# ProPrj_MPY634__2025-07-24.net
KiCad netlist of a schematic drawn in EasyEDA Pro
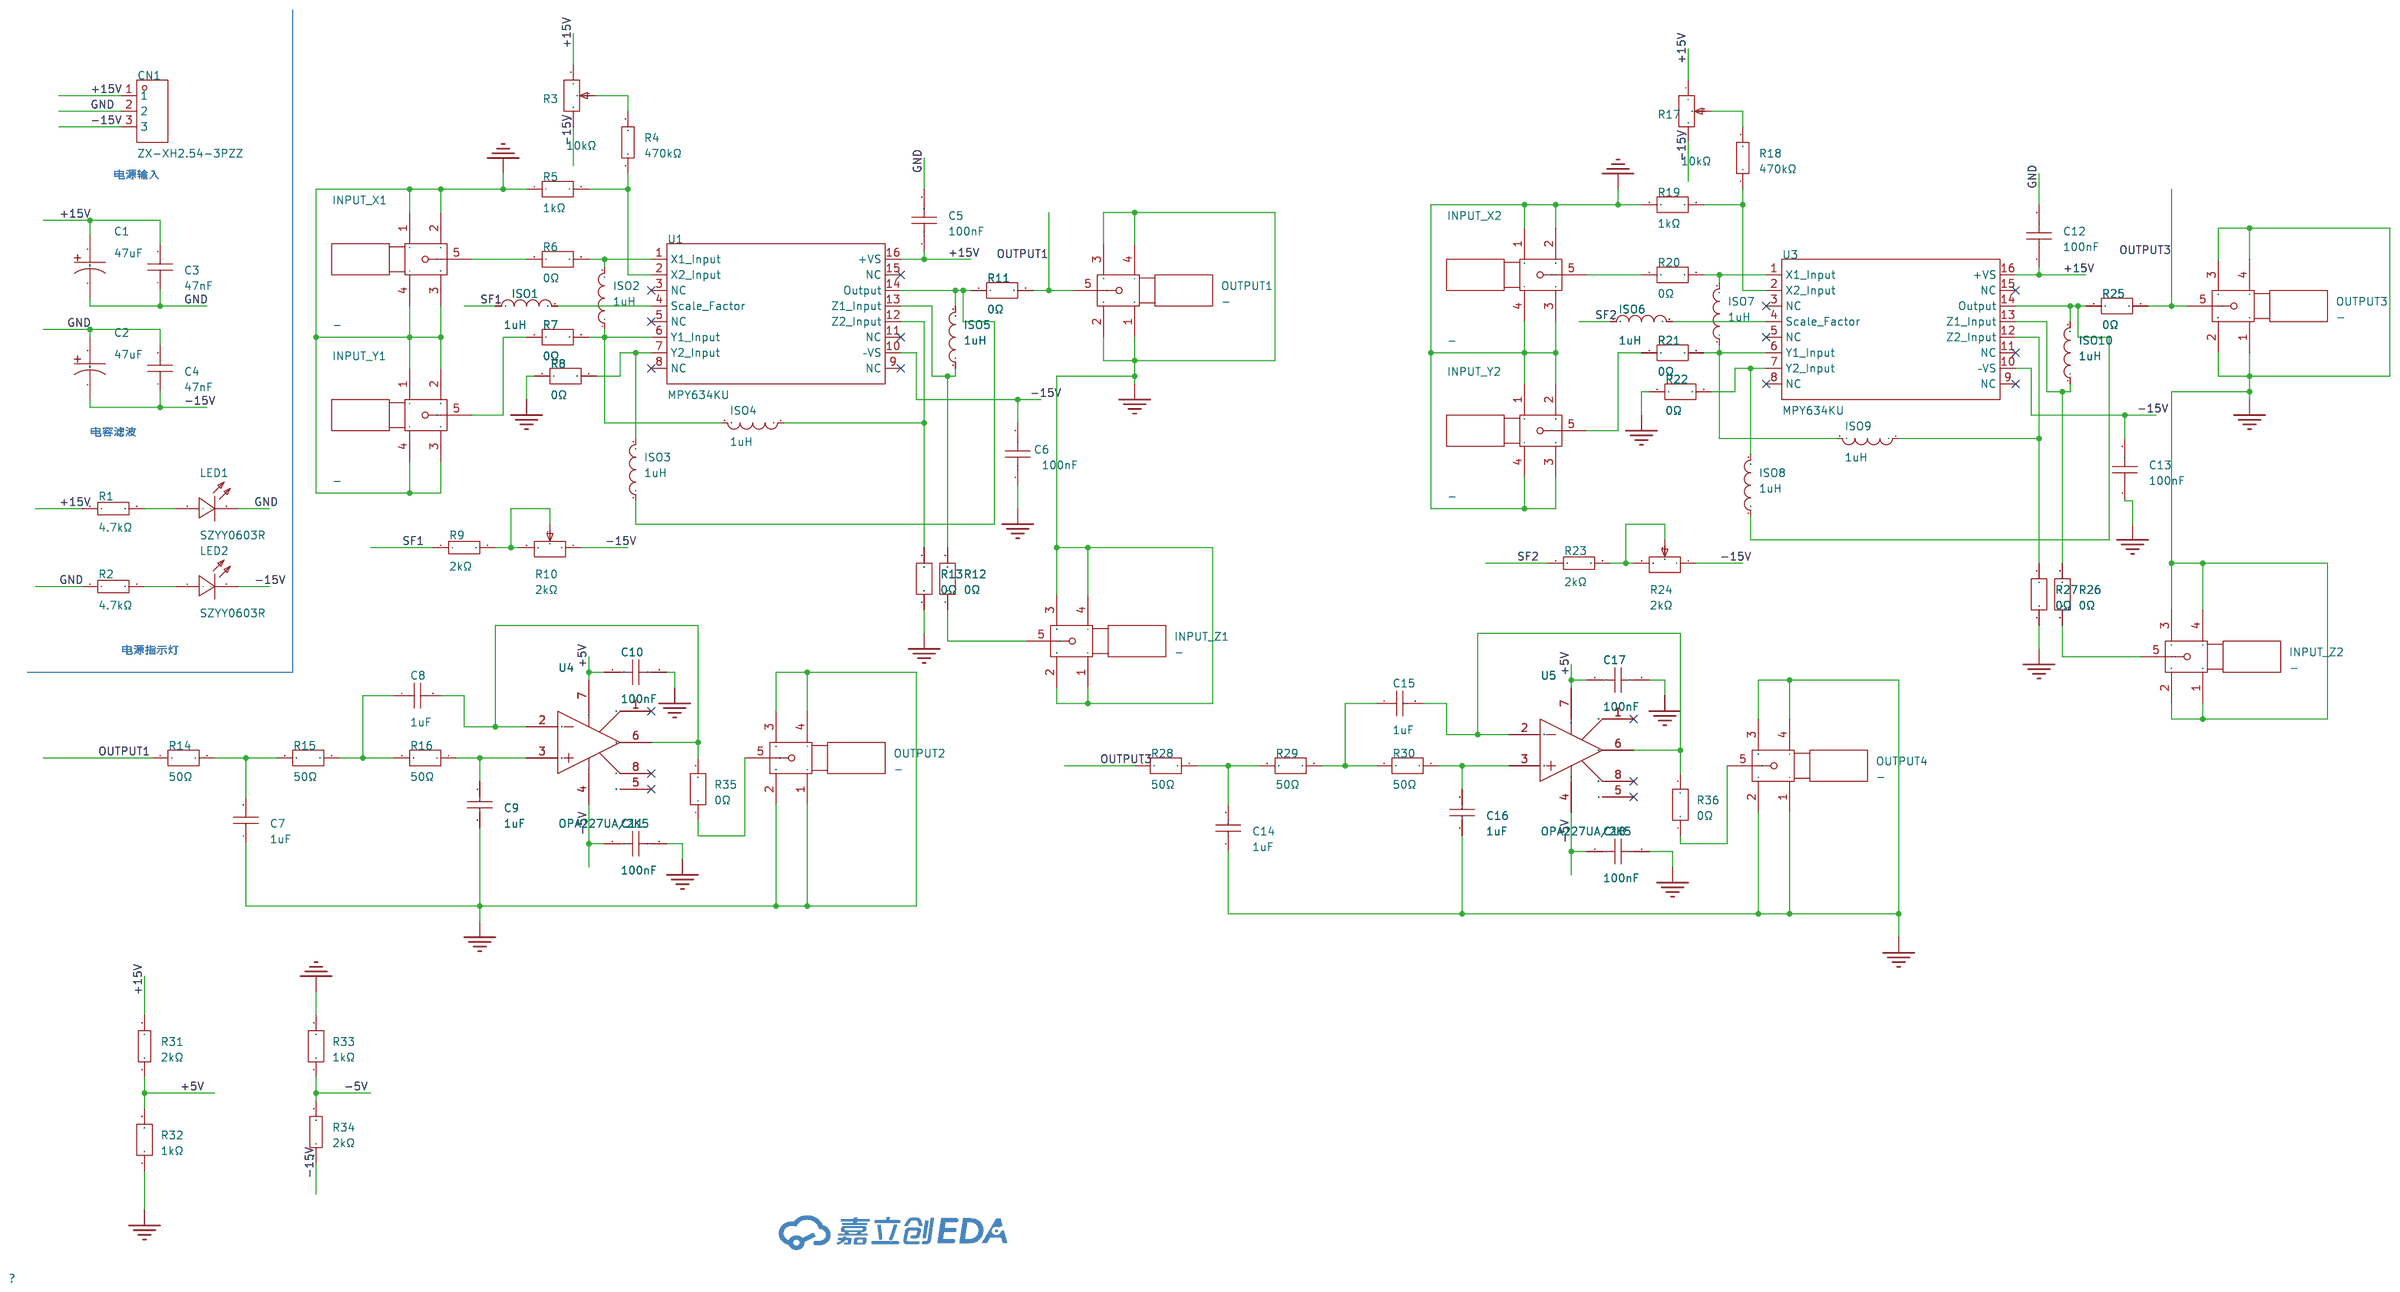
[diagram p0: schematic sheet]

(export (version "E")
  (design (tool "Eeschema 10.0.6"))
  (components
    (comp (ref "C1")
      (value "47uF")
      (footprint "easyedapro:CAP-TH_BD5.0-P2.00-D0.8-FD")
      (description "容值:47uF;精度:±20%;额定电压:25V;纹波电流:250mA@100kHz;等效串联电阻(ESR):300mΩ@100kHz;")
      (fields
        (field (name "Manufacturer Part") "NXB25V47M5*11 2.5TP")
        (field (name "Manufacturer") "SAMYOUNG(韩国三莹)")
      )
      (libsource (lib "easyedapro") (part "NXB25VB47M5*11_2.5TP"))
    )
    (comp (ref "C2")
      (value "47uF")
      (footprint "easyedapro:CAP-TH_BD5.0-P2.00-D0.8-FD")
      (description "容值:47uF;精度:±20%;额定电压:25V;纹波电流:250mA@100kHz;等效串联电阻(ESR):300mΩ@100kHz;")
      (fields
        (field (name "Manufacturer Part") "NXB25V47M5*11 2.5TP")
        (field (name "Manufacturer") "SAMYOUNG(韩国三莹)")
      )
      (libsource (lib "easyedapro") (part "NXB25VB47M5*11_2.5TP"))
    )
    (comp (ref "C3")
      (value "47nF")
      (footprint "easyedapro:C0805")
      (description "容值:47nF;精度:±10%;额定电压:50V;材质(温度系数):X7R;")
      (fields
        (field (name "Manufacturer Part") "CL21B473KBCNNNC")
        (field (name "Manufacturer") "SAMSUNG(三星)")
      )
      (libsource (lib "easyedapro") (part "CL21B473KBCNNNC"))
    )
    (comp (ref "C4")
      (value "47nF")
      (footprint "easyedapro:C0805")
      (description "容值:47nF;精度:±10%;额定电压:50V;材质(温度系数):X7R;")
      (fields
        (field (name "Manufacturer Part") "CL21B473KBCNNNC")
        (field (name "Manufacturer") "SAMSUNG(三星)")
      )
      (libsource (lib "easyedapro") (part "CL21B473KBCNNNC"))
    )
    (comp (ref "C5")
      (value "100nF")
      (footprint "easyedapro:C0805")
      (description "容值:100nF;精度:±10%;额定电压:50V;材质(温度系数):X7R;")
      (fields
        (field (name "Manufacturer Part") "CC0805KRX7R9BB104")
        (field (name "Manufacturer") "YAGEO(国巨)")
      )
      (libsource (lib "easyedapro") (part "CC0805KRX7R9BB104"))
    )
    (comp (ref "C6")
      (value "100nF")
      (footprint "easyedapro:C0805")
      (description "容值:100nF;精度:±10%;额定电压:50V;材质(温度系数):X7R;")
      (fields
        (field (name "Manufacturer Part") "CC0805KRX7R9BB104")
        (field (name "Manufacturer") "YAGEO(国巨)")
      )
      (libsource (lib "easyedapro") (part "CC0805KRX7R9BB104"))
    )
    (comp (ref "C7")
      (value "1uF")
      (footprint "easyedapro:C0805")
      (description "容值:1uF;精度:±10%;额定电压:50V;材质(温度系数):X7R;")
      (fields
        (field (name "Manufacturer Part") "CL21B105KBFNNNE")
        (field (name "Manufacturer") "SAMSUNG(三星)")
      )
      (libsource (lib "easyedapro") (part "CL21B105KBFNNNE"))
    )
    (comp (ref "C8")
      (value "1uF")
      (footprint "easyedapro:C0805")
      (description "容值:1uF;精度:±10%;额定电压:50V;材质(温度系数):X7R;")
      (fields
        (field (name "Manufacturer Part") "CL21B105KBFNNNE")
        (field (name "Manufacturer") "SAMSUNG(三星)")
      )
      (libsource (lib "easyedapro") (part "CL21B105KBFNNNE"))
    )
    (comp (ref "C9")
      (value "1uF")
      (footprint "easyedapro:C0805")
      (description "容值:1uF;精度:±10%;额定电压:50V;材质(温度系数):X7R;")
      (fields
        (field (name "Manufacturer Part") "CL21B105KBFNNNE")
        (field (name "Manufacturer") "SAMSUNG(三星)")
      )
      (libsource (lib "easyedapro") (part "CL21B105KBFNNNE"))
    )
    (comp (ref "C10")
      (value "100nF")
      (footprint "easyedapro:C0805")
      (description "容值:100nF;精度:±10%;额定电压:50V;材质(温度系数):X7R;")
      (fields
        (field (name "Manufacturer Part") "CC0805KRX7R9BB104")
        (field (name "Manufacturer") "YAGEO(国巨)")
      )
      (libsource (lib "easyedapro") (part "CC0805KRX7R9BB104"))
    )
    (comp (ref "C11")
      (value "100nF")
      (footprint "easyedapro:C0805")
      (description "容值:100nF;精度:±10%;额定电压:50V;材质(温度系数):X7R;")
      (fields
        (field (name "Manufacturer Part") "CC0805KRX7R9BB104")
        (field (name "Manufacturer") "YAGEO(国巨)")
      )
      (libsource (lib "easyedapro") (part "CC0805KRX7R9BB104"))
    )
    (comp (ref "C12")
      (value "100nF")
      (footprint "easyedapro:C0805")
      (description "容值:100nF;精度:±10%;额定电压:50V;材质(温度系数):X7R;")
      (fields
        (field (name "Manufacturer Part") "CC0805KRX7R9BB104")
        (field (name "Manufacturer") "YAGEO(国巨)")
      )
      (libsource (lib "easyedapro") (part "CC0805KRX7R9BB104"))
    )
    (comp (ref "C13")
      (value "100nF")
      (footprint "easyedapro:C0805")
      (description "容值:100nF;精度:±10%;额定电压:50V;材质(温度系数):X7R;")
      (fields
        (field (name "Manufacturer Part") "CC0805KRX7R9BB104")
        (field (name "Manufacturer") "YAGEO(国巨)")
      )
      (libsource (lib "easyedapro") (part "CC0805KRX7R9BB104"))
    )
    (comp (ref "C14")
      (value "1uF")
      (footprint "easyedapro:C0805")
      (description "容值:1uF;精度:±10%;额定电压:50V;材质(温度系数):X7R;")
      (fields
        (field (name "Manufacturer Part") "CL21B105KBFNNNE")
        (field (name "Manufacturer") "SAMSUNG(三星)")
      )
      (libsource (lib "easyedapro") (part "CL21B105KBFNNNE"))
    )
    (comp (ref "C15")
      (value "1uF")
      (footprint "easyedapro:C0805")
      (description "容值:1uF;精度:±10%;额定电压:50V;材质(温度系数):X7R;")
      (fields
        (field (name "Manufacturer Part") "CL21B105KBFNNNE")
        (field (name "Manufacturer") "SAMSUNG(三星)")
      )
      (libsource (lib "easyedapro") (part "CL21B105KBFNNNE"))
    )
    (comp (ref "C16")
      (value "1uF")
      (footprint "easyedapro:C0805")
      (description "容值:1uF;精度:±10%;额定电压:50V;材质(温度系数):X7R;")
      (fields
        (field (name "Manufacturer Part") "CL21B105KBFNNNE")
        (field (name "Manufacturer") "SAMSUNG(三星)")
      )
      (libsource (lib "easyedapro") (part "CL21B105KBFNNNE"))
    )
    (comp (ref "C17")
      (value "100nF")
      (footprint "easyedapro:C0805")
      (description "容值:100nF;精度:±10%;额定电压:50V;材质(温度系数):X7R;")
      (fields
        (field (name "Manufacturer Part") "CC0805KRX7R9BB104")
        (field (name "Manufacturer") "YAGEO(国巨)")
      )
      (libsource (lib "easyedapro") (part "CC0805KRX7R9BB104"))
    )
    (comp (ref "C18")
      (value "100nF")
      (footprint "easyedapro:C0805")
      (description "容值:100nF;精度:±10%;额定电压:50V;材质(温度系数):X7R;")
      (fields
        (field (name "Manufacturer Part") "CC0805KRX7R9BB104")
        (field (name "Manufacturer") "YAGEO(国巨)")
      )
      (libsource (lib "easyedapro") (part "CC0805KRX7R9BB104"))
    )
    (comp (ref "CN1")
      (value "ZX-XH2.54-3PZZ")
      (footprint "easyedapro:CONN-TH_3P-P2.54_2501S-3P")
      (fields (field (name "Manufacturer") "Megastar(兆星)"))
      (libsource (lib "easyedapro") (part "ZX-XH2.54-3PZZ"))
    )
    (comp (ref "INPUT_X1")
      (value "-")
      (footprint "easyedapro:SMA-SMD_BWSMA-KE-P001")
      (description "连接器类型:板端;接口类型:内孔;端口数量:1;接口直径:5.2mm;接口长度/高度:-;频率:-;射频系列:SMA;阻抗:50Ω;样式:偏脚;工作温度:-;")
      (fields
        (field (name "Manufacturer Part") "BWSMA-KE-P001")
        (field (name "Manufacturer") "BAT WIRELESS(蝙蝠无线)")
      )
      (libsource (lib "easyedapro") (part "BWSMA-KE-P001"))
    )
    (comp (ref "INPUT_X2")
      (value "-")
      (footprint "easyedapro:SMA-SMD_BWSMA-KE-P001")
      (description "连接器类型:板端;接口类型:内孔;端口数量:1;接口直径:5.2mm;接口长度/高度:-;频率:-;射频系列:SMA;阻抗:50Ω;样式:偏脚;工作温度:-;")
      (fields
        (field (name "Manufacturer Part") "BWSMA-KE-P001")
        (field (name "Manufacturer") "BAT WIRELESS(蝙蝠无线)")
      )
      (libsource (lib "easyedapro") (part "BWSMA-KE-P001"))
    )
    (comp (ref "INPUT_Y1")
      (value "-")
      (footprint "easyedapro:SMA-SMD_BWSMA-KE-P001")
      (description "连接器类型:板端;接口类型:内孔;端口数量:1;接口直径:5.2mm;接口长度/高度:-;频率:-;射频系列:SMA;阻抗:50Ω;样式:偏脚;工作温度:-;")
      (fields
        (field (name "Manufacturer Part") "BWSMA-KE-P001")
        (field (name "Manufacturer") "BAT WIRELESS(蝙蝠无线)")
      )
      (libsource (lib "easyedapro") (part "BWSMA-KE-P001"))
    )
    (comp (ref "INPUT_Y2")
      (value "-")
      (footprint "easyedapro:SMA-SMD_BWSMA-KE-P001")
      (description "连接器类型:板端;接口类型:内孔;端口数量:1;接口直径:5.2mm;接口长度/高度:-;频率:-;射频系列:SMA;阻抗:50Ω;样式:偏脚;工作温度:-;")
      (fields
        (field (name "Manufacturer Part") "BWSMA-KE-P001")
        (field (name "Manufacturer") "BAT WIRELESS(蝙蝠无线)")
      )
      (libsource (lib "easyedapro") (part "BWSMA-KE-P001"))
    )
    (comp (ref "INPUT_Z1")
      (value "-")
      (footprint "easyedapro:SMA-SMD_BWSMA-KE-P001")
      (description "连接器类型:板端;接口类型:内孔;端口数量:1;接口直径:5.2mm;接口长度/高度:-;频率:-;射频系列:SMA;阻抗:50Ω;样式:偏脚;工作温度:-;")
      (fields
        (field (name "Manufacturer Part") "BWSMA-KE-P001")
        (field (name "Manufacturer") "BAT WIRELESS(蝙蝠无线)")
      )
      (libsource (lib "easyedapro") (part "BWSMA-KE-P001"))
    )
    (comp (ref "INPUT_Z2")
      (value "-")
      (footprint "easyedapro:SMA-SMD_BWSMA-KE-P001")
      (description "连接器类型:板端;接口类型:内孔;端口数量:1;接口直径:5.2mm;接口长度/高度:-;频率:-;射频系列:SMA;阻抗:50Ω;样式:偏脚;工作温度:-;")
      (fields
        (field (name "Manufacturer Part") "BWSMA-KE-P001")
        (field (name "Manufacturer") "BAT WIRELESS(蝙蝠无线)")
      )
      (libsource (lib "easyedapro") (part "BWSMA-KE-P001"))
    )
    (comp (ref "ISO1")
      (value "1uH")
      (footprint "easyedapro:IND-SMD_L1.0-W0.6")
      (description "电感值:1uH;精度:±20%;额定电流:270mA;饱和电流(Isat):-;")
      (fields (field (name "Manufacturer Part") "LQW15CN1R0M10D") (field (name "Manufacturer") "muRata(村田)"))
      (libsource (lib "easyedapro") (part "LQW15CN1R0M10D"))
    )
    (comp (ref "ISO2")
      (value "1uH")
      (footprint "easyedapro:IND-SMD_L1.0-W0.6")
      (description "电感值:1uH;精度:±20%;额定电流:270mA;饱和电流(Isat):-;")
      (fields (field (name "Manufacturer Part") "LQW15CN1R0M10D") (field (name "Manufacturer") "muRata(村田)"))
      (libsource (lib "easyedapro") (part "LQW15CN1R0M10D"))
    )
    (comp (ref "ISO3")
      (value "1uH")
      (footprint "easyedapro:IND-SMD_L1.0-W0.6")
      (description "电感值:1uH;精度:±20%;额定电流:270mA;饱和电流(Isat):-;")
      (fields (field (name "Manufacturer Part") "LQW15CN1R0M10D") (field (name "Manufacturer") "muRata(村田)"))
      (libsource (lib "easyedapro") (part "LQW15CN1R0M10D"))
    )
    (comp (ref "ISO4")
      (value "1uH")
      (footprint "easyedapro:IND-SMD_L1.0-W0.6")
      (description "电感值:1uH;精度:±20%;额定电流:270mA;饱和电流(Isat):-;")
      (fields (field (name "Manufacturer Part") "LQW15CN1R0M10D") (field (name "Manufacturer") "muRata(村田)"))
      (libsource (lib "easyedapro") (part "LQW15CN1R0M10D"))
    )
    (comp (ref "ISO5")
      (value "1uH")
      (footprint "easyedapro:IND-SMD_L1.0-W0.6")
      (description "电感值:1uH;精度:±20%;额定电流:270mA;饱和电流(Isat):-;")
      (fields (field (name "Manufacturer Part") "LQW15CN1R0M10D") (field (name "Manufacturer") "muRata(村田)"))
      (libsource (lib "easyedapro") (part "LQW15CN1R0M10D"))
    )
    (comp (ref "ISO6")
      (value "1uH")
      (footprint "easyedapro:IND-SMD_L1.0-W0.6")
      (description "电感值:1uH;精度:±20%;额定电流:270mA;饱和电流(Isat):-;")
      (fields (field (name "Manufacturer Part") "LQW15CN1R0M10D") (field (name "Manufacturer") "muRata(村田)"))
      (libsource (lib "easyedapro") (part "LQW15CN1R0M10D"))
    )
    (comp (ref "ISO7")
      (value "1uH")
      (footprint "easyedapro:IND-SMD_L1.0-W0.6")
      (description "电感值:1uH;精度:±20%;额定电流:270mA;饱和电流(Isat):-;")
      (fields (field (name "Manufacturer Part") "LQW15CN1R0M10D") (field (name "Manufacturer") "muRata(村田)"))
      (libsource (lib "easyedapro") (part "LQW15CN1R0M10D"))
    )
    (comp (ref "ISO8")
      (value "1uH")
      (footprint "easyedapro:IND-SMD_L1.0-W0.6")
      (description "电感值:1uH;精度:±20%;额定电流:270mA;饱和电流(Isat):-;")
      (fields (field (name "Manufacturer Part") "LQW15CN1R0M10D") (field (name "Manufacturer") "muRata(村田)"))
      (libsource (lib "easyedapro") (part "LQW15CN1R0M10D"))
    )
    (comp (ref "ISO9")
      (value "1uH")
      (footprint "easyedapro:IND-SMD_L1.0-W0.6")
      (description "电感值:1uH;精度:±20%;额定电流:270mA;饱和电流(Isat):-;")
      (fields (field (name "Manufacturer Part") "LQW15CN1R0M10D") (field (name "Manufacturer") "muRata(村田)"))
      (libsource (lib "easyedapro") (part "LQW15CN1R0M10D"))
    )
    (comp (ref "ISO10")
      (value "1uH")
      (footprint "easyedapro:IND-SMD_L1.0-W0.6")
      (description "电感值:1uH;精度:±20%;额定电流:270mA;饱和电流(Isat):-;")
      (fields (field (name "Manufacturer Part") "LQW15CN1R0M10D") (field (name "Manufacturer") "muRata(村田)"))
      (libsource (lib "easyedapro") (part "LQW15CN1R0M10D"))
    )
    (comp (ref "LED1")
      (value "SZYY0603R")
      (footprint "easyedapro:LED0603-R-RD")
      (fields (field (name "Manufacturer") "yongyu(永裕光电)"))
      (libsource (lib "easyedapro") (part "SZYY0603R"))
    )
    (comp (ref "LED2")
      (value "SZYY0603R")
      (footprint "easyedapro:LED0603-R-RD")
      (fields (field (name "Manufacturer") "yongyu(永裕光电)"))
      (libsource (lib "easyedapro") (part "SZYY0603R"))
    )
    (comp (ref "OUTPUT1")
      (value "-")
      (footprint "easyedapro:SMA-SMD_BWSMA-KE-P001")
      (description "连接器类型:板端;接口类型:内孔;端口数量:1;接口直径:5.2mm;接口长度/高度:-;频率:-;射频系列:SMA;阻抗:50Ω;样式:偏脚;工作温度:-;")
      (fields
        (field (name "Manufacturer Part") "BWSMA-KE-P001")
        (field (name "Manufacturer") "BAT WIRELESS(蝙蝠无线)")
      )
      (libsource (lib "easyedapro") (part "BWSMA-KE-P001"))
    )
    (comp (ref "OUTPUT2")
      (value "-")
      (footprint "easyedapro:SMA-SMD_BWSMA-KE-P001")
      (description "连接器类型:板端;接口类型:内孔;端口数量:1;接口直径:5.2mm;接口长度/高度:-;频率:-;射频系列:SMA;阻抗:50Ω;样式:偏脚;工作温度:-;")
      (fields
        (field (name "Manufacturer Part") "BWSMA-KE-P001")
        (field (name "Manufacturer") "BAT WIRELESS(蝙蝠无线)")
      )
      (libsource (lib "easyedapro") (part "BWSMA-KE-P001"))
    )
    (comp (ref "OUTPUT3")
      (value "-")
      (footprint "easyedapro:SMA-SMD_BWSMA-KE-P001")
      (description "连接器类型:板端;接口类型:内孔;端口数量:1;接口直径:5.2mm;接口长度/高度:-;频率:-;射频系列:SMA;阻抗:50Ω;样式:偏脚;工作温度:-;")
      (fields
        (field (name "Manufacturer Part") "BWSMA-KE-P001")
        (field (name "Manufacturer") "BAT WIRELESS(蝙蝠无线)")
      )
      (libsource (lib "easyedapro") (part "BWSMA-KE-P001"))
    )
    (comp (ref "OUTPUT4")
      (value "-")
      (footprint "easyedapro:SMA-SMD_BWSMA-KE-P001")
      (description "连接器类型:板端;接口类型:内孔;端口数量:1;接口直径:5.2mm;接口长度/高度:-;频率:-;射频系列:SMA;阻抗:50Ω;样式:偏脚;工作温度:-;")
      (fields
        (field (name "Manufacturer Part") "BWSMA-KE-P001")
        (field (name "Manufacturer") "BAT WIRELESS(蝙蝠无线)")
      )
      (libsource (lib "easyedapro") (part "BWSMA-KE-P001"))
    )
    (comp (ref "R1")
      (value "4.7kΩ")
      (footprint "easyedapro:R0805")
      (description "电阻类型:厚膜电阻;阻值:4.7kΩ;精度:±1%;功率:125mW;最大工作电压:150V;温度系数:±100ppm/°C;")
      (fields
        (field (name "Manufacturer Part") "0805W8F4701T5E")
        (field (name "Manufacturer") "UNI-ROYAL(厚声)")
      )
      (libsource (lib "easyedapro") (part "0805W8F4701T5E"))
    )
    (comp (ref "R2")
      (value "4.7kΩ")
      (footprint "easyedapro:R0805")
      (description "电阻类型:厚膜电阻;阻值:4.7kΩ;精度:±1%;功率:125mW;最大工作电压:150V;温度系数:±100ppm/°C;")
      (fields
        (field (name "Manufacturer Part") "0805W8F4701T5E")
        (field (name "Manufacturer") "UNI-ROYAL(厚声)")
      )
      (libsource (lib "easyedapro") (part "0805W8F4701T5E"))
    )
    (comp (ref "R3")
      (value "10kΩ")
      (footprint "easyedapro:RES-ADJ-TH_3296W")
      (description "阻值:10kΩ;精度:±10%;功率:500mW;温度系数:±100ppm/°C;")
      (fields (field (name "Manufacturer Part") "3296W-1-103LF") (field (name "Manufacturer") "BOURNS"))
      (libsource (lib "easyedapro") (part "3296W-1-103LF"))
    )
    (comp (ref "R4")
      (value "470kΩ")
      (footprint "easyedapro:R0805")
      (description "电阻类型:厚膜电阻;阻值:470kΩ;精度:±1%;功率:125mW;最大工作电压:150V;温度系数:±100ppm/°C;")
      (fields
        (field (name "Manufacturer Part") "0805W8F4703T5E")
        (field (name "Manufacturer") "UNI-ROYAL(厚声)")
      )
      (libsource (lib "easyedapro") (part "0805W8F4703T5E"))
    )
    (comp (ref "R5")
      (value "1kΩ")
      (footprint "easyedapro:R0805")
      (description "电阻类型:厚膜电阻;阻值:1kΩ;精度:±5%;功率:125mW;最大工作电压:150V;温度系数:±100ppm/°C;")
      (fields (field (name "Manufacturer Part") "FRC0805J102 TS") (field (name "Manufacturer") "FOJAN(富捷)"))
      (libsource (lib "easyedapro") (part "FRC0805J102 TS"))
    )
    (comp (ref "R6")
      (value "0Ω")
      (footprint "easyedapro:R0603")
      (description "电阻类型:厚膜电阻;阻值:0Ω;精度:±5%;功率:100mW;最大工作电压:75V;")
      (fields (field (name "Manufacturer Part") "FRC0603P000 TS") (field (name "Manufacturer") "FOJAN(富捷)"))
      (libsource (lib "easyedapro") (part "FRC0603P000 TS"))
    )
    (comp (ref "R7")
      (value "0Ω")
      (footprint "easyedapro:R0603")
      (description "电阻类型:厚膜电阻;阻值:0Ω;精度:±5%;功率:100mW;最大工作电压:75V;")
      (fields (field (name "Manufacturer Part") "FRC0603P000 TS") (field (name "Manufacturer") "FOJAN(富捷)"))
      (libsource (lib "easyedapro") (part "FRC0603P000 TS"))
    )
    (comp (ref "R8")
      (value "0Ω")
      (footprint "easyedapro:R0603")
      (description "电阻类型:厚膜电阻;阻值:0Ω;精度:±5%;功率:100mW;最大工作电压:75V;")
      (fields (field (name "Manufacturer Part") "FRC0603P000 TS") (field (name "Manufacturer") "FOJAN(富捷)"))
      (libsource (lib "easyedapro") (part "FRC0603P000 TS"))
    )
    (comp (ref "R9")
      (value "2kΩ")
      (footprint "easyedapro:R0805")
      (description "电阻类型:厚膜电阻;阻值:2kΩ;精度:±1%;功率:125mW;最大工作电压:150V;温度系数:±100ppm/°C;")
      (fields
        (field (name "Manufacturer Part") "0805W8F2001T5E")
        (field (name "Manufacturer") "UNI-ROYAL(厚声)")
      )
      (libsource (lib "easyedapro") (part "0805W8F2001T5E"))
    )
    (comp (ref "R10")
      (value "2kΩ")
      (footprint "easyedapro:RES-ADJ-TH_3296W")
      (description "阻值:2kΩ;精度:±10%;")
      (fields (field (name "Manufacturer Part") "3296W-1-202LF") (field (name "Manufacturer") "BOURNS"))
      (libsource (lib "easyedapro") (part "3296W-1-202LF_C83684"))
    )
    (comp (ref "R11")
      (value "0Ω")
      (footprint "easyedapro:R0603")
      (description "电阻类型:厚膜电阻;阻值:0Ω;精度:±5%;功率:100mW;最大工作电压:75V;")
      (fields (field (name "Manufacturer Part") "FRC0603P000 TS") (field (name "Manufacturer") "FOJAN(富捷)"))
      (libsource (lib "easyedapro") (part "FRC0603P000 TS"))
    )
    (comp (ref "R12")
      (value "0Ω")
      (footprint "easyedapro:R0603")
      (description "电阻类型:厚膜电阻;阻值:0Ω;精度:±5%;功率:100mW;最大工作电压:75V;")
      (fields (field (name "Manufacturer Part") "FRC0603P000 TS") (field (name "Manufacturer") "FOJAN(富捷)"))
      (libsource (lib "easyedapro") (part "FRC0603P000 TS"))
    )
    (comp (ref "R13")
      (value "0Ω")
      (footprint "easyedapro:R0603")
      (description "电阻类型:厚膜电阻;阻值:0Ω;精度:±5%;功率:100mW;最大工作电压:75V;")
      (fields (field (name "Manufacturer Part") "FRC0603P000 TS") (field (name "Manufacturer") "FOJAN(富捷)"))
      (libsource (lib "easyedapro") (part "FRC0603P000 TS"))
    )
    (comp (ref "R14")
      (value "50Ω")
      (footprint "easyedapro:R0805")
      (description "电阻类型:薄膜电阻;阻值:50Ω;精度:±0.1%;功率:100mW;温度系数:±25ppm/°C;")
      (fields (field (name "Manufacturer Part") "TD05G50R0BT") (field (name "Manufacturer") "FH(风华)"))
      (libsource (lib "easyedapro") (part "TD05G50R0BT"))
    )
    (comp (ref "R15")
      (value "50Ω")
      (footprint "easyedapro:R0805")
      (description "电阻类型:薄膜电阻;阻值:50Ω;精度:±0.1%;功率:100mW;温度系数:±25ppm/°C;")
      (fields (field (name "Manufacturer Part") "TD05G50R0BT") (field (name "Manufacturer") "FH(风华)"))
      (libsource (lib "easyedapro") (part "TD05G50R0BT"))
    )
    (comp (ref "R16")
      (value "50Ω")
      (footprint "easyedapro:R0805")
      (description "电阻类型:薄膜电阻;阻值:50Ω;精度:±0.1%;功率:100mW;温度系数:±25ppm/°C;")
      (fields (field (name "Manufacturer Part") "TD05G50R0BT") (field (name "Manufacturer") "FH(风华)"))
      (libsource (lib "easyedapro") (part "TD05G50R0BT"))
    )
    (comp (ref "R17")
      (value "10kΩ")
      (footprint "easyedapro:RES-ADJ-TH_3296W")
      (description "阻值:10kΩ;精度:±10%;功率:500mW;温度系数:±100ppm/°C;")
      (fields (field (name "Manufacturer Part") "3296W-1-103LF") (field (name "Manufacturer") "BOURNS"))
      (libsource (lib "easyedapro") (part "3296W-1-103LF"))
    )
    (comp (ref "R18")
      (value "470kΩ")
      (footprint "easyedapro:R0805")
      (description "电阻类型:厚膜电阻;阻值:470kΩ;精度:±1%;功率:125mW;最大工作电压:150V;温度系数:±100ppm/°C;")
      (fields
        (field (name "Manufacturer Part") "0805W8F4703T5E")
        (field (name "Manufacturer") "UNI-ROYAL(厚声)")
      )
      (libsource (lib "easyedapro") (part "0805W8F4703T5E"))
    )
    (comp (ref "R19")
      (value "1kΩ")
      (footprint "easyedapro:R0805")
      (description "电阻类型:厚膜电阻;阻值:1kΩ;精度:±5%;功率:125mW;最大工作电压:150V;温度系数:±100ppm/°C;")
      (fields (field (name "Manufacturer Part") "FRC0805J102 TS") (field (name "Manufacturer") "FOJAN(富捷)"))
      (libsource (lib "easyedapro") (part "FRC0805J102 TS"))
    )
    (comp (ref "R20")
      (value "0Ω")
      (footprint "easyedapro:R0603")
      (description "电阻类型:厚膜电阻;阻值:0Ω;精度:±5%;功率:100mW;最大工作电压:75V;")
      (fields (field (name "Manufacturer Part") "FRC0603P000 TS") (field (name "Manufacturer") "FOJAN(富捷)"))
      (libsource (lib "easyedapro") (part "FRC0603P000 TS"))
    )
    (comp (ref "R21")
      (value "0Ω")
      (footprint "easyedapro:R0603")
      (description "电阻类型:厚膜电阻;阻值:0Ω;精度:±5%;功率:100mW;最大工作电压:75V;")
      (fields (field (name "Manufacturer Part") "FRC0603P000 TS") (field (name "Manufacturer") "FOJAN(富捷)"))
      (libsource (lib "easyedapro") (part "FRC0603P000 TS"))
    )
    (comp (ref "R22")
      (value "0Ω")
      (footprint "easyedapro:R0603")
      (description "电阻类型:厚膜电阻;阻值:0Ω;精度:±5%;功率:100mW;最大工作电压:75V;")
      (fields (field (name "Manufacturer Part") "FRC0603P000 TS") (field (name "Manufacturer") "FOJAN(富捷)"))
      (libsource (lib "easyedapro") (part "FRC0603P000 TS"))
    )
    (comp (ref "R23")
      (value "2kΩ")
      (footprint "easyedapro:R0805")
      (description "电阻类型:厚膜电阻;阻值:2kΩ;精度:±1%;功率:125mW;最大工作电压:150V;温度系数:±100ppm/°C;")
      (fields
        (field (name "Manufacturer Part") "0805W8F2001T5E")
        (field (name "Manufacturer") "UNI-ROYAL(厚声)")
      )
      (libsource (lib "easyedapro") (part "0805W8F2001T5E"))
    )
    (comp (ref "R24")
      (value "2kΩ")
      (footprint "easyedapro:RES-ADJ-TH_3296W")
      (description "阻值:2kΩ;精度:±10%;")
      (fields (field (name "Manufacturer Part") "3296W-1-202LF") (field (name "Manufacturer") "BOURNS"))
      (libsource (lib "easyedapro") (part "3296W-1-202LF_C83684"))
    )
    (comp (ref "R25")
      (value "0Ω")
      (footprint "easyedapro:R0603")
      (description "电阻类型:厚膜电阻;阻值:0Ω;精度:±5%;功率:100mW;最大工作电压:75V;")
      (fields (field (name "Manufacturer Part") "FRC0603P000 TS") (field (name "Manufacturer") "FOJAN(富捷)"))
      (libsource (lib "easyedapro") (part "FRC0603P000 TS"))
    )
    (comp (ref "R26")
      (value "0Ω")
      (footprint "easyedapro:R0603")
      (description "电阻类型:厚膜电阻;阻值:0Ω;精度:±5%;功率:100mW;最大工作电压:75V;")
      (fields (field (name "Manufacturer Part") "FRC0603P000 TS") (field (name "Manufacturer") "FOJAN(富捷)"))
      (libsource (lib "easyedapro") (part "FRC0603P000 TS"))
    )
    (comp (ref "R27")
      (value "0Ω")
      (footprint "easyedapro:R0603")
      (description "电阻类型:厚膜电阻;阻值:0Ω;精度:±5%;功率:100mW;最大工作电压:75V;")
      (fields (field (name "Manufacturer Part") "FRC0603P000 TS") (field (name "Manufacturer") "FOJAN(富捷)"))
      (libsource (lib "easyedapro") (part "FRC0603P000 TS"))
    )
    (comp (ref "R28")
      (value "50Ω")
      (footprint "easyedapro:R0805")
      (description "电阻类型:薄膜电阻;阻值:50Ω;精度:±0.1%;功率:100mW;温度系数:±25ppm/°C;")
      (fields (field (name "Manufacturer Part") "TD05G50R0BT") (field (name "Manufacturer") "FH(风华)"))
      (libsource (lib "easyedapro") (part "TD05G50R0BT"))
    )
    (comp (ref "R29")
      (value "50Ω")
      (footprint "easyedapro:R0805")
      (description "电阻类型:薄膜电阻;阻值:50Ω;精度:±0.1%;功率:100mW;温度系数:±25ppm/°C;")
      (fields (field (name "Manufacturer Part") "TD05G50R0BT") (field (name "Manufacturer") "FH(风华)"))
      (libsource (lib "easyedapro") (part "TD05G50R0BT"))
    )
    (comp (ref "R30")
      (value "50Ω")
      (footprint "easyedapro:R0805")
      (description "电阻类型:薄膜电阻;阻值:50Ω;精度:±0.1%;功率:100mW;温度系数:±25ppm/°C;")
      (fields (field (name "Manufacturer Part") "TD05G50R0BT") (field (name "Manufacturer") "FH(风华)"))
      (libsource (lib "easyedapro") (part "TD05G50R0BT"))
    )
    (comp (ref "R31")
      (value "2kΩ")
      (footprint "easyedapro:R0805")
      (description "电阻类型:厚膜电阻;阻值:2kΩ;精度:±1%;功率:125mW;最大工作电压:150V;温度系数:±100ppm/°C;")
      (fields
        (field (name "Manufacturer Part") "0805W8F2001T5E")
        (field (name "Manufacturer") "UNI-ROYAL(厚声)")
      )
      (libsource (lib "easyedapro") (part "0805W8F2001T5E"))
    )
    (comp (ref "R32")
      (value "1kΩ")
      (footprint "easyedapro:R0805")
      (description "电阻类型:厚膜电阻;阻值:1kΩ;精度:±5%;功率:125mW;最大工作电压:150V;温度系数:±100ppm/°C;")
      (fields (field (name "Manufacturer Part") "FRC0805J102 TS") (field (name "Manufacturer") "FOJAN(富捷)"))
      (libsource (lib "easyedapro") (part "FRC0805J102 TS"))
    )
    (comp (ref "R33")
      (value "1kΩ")
      (footprint "easyedapro:R0805")
      (description "电阻类型:厚膜电阻;阻值:1kΩ;精度:±5%;功率:125mW;最大工作电压:150V;温度系数:±100ppm/°C;")
      (fields (field (name "Manufacturer Part") "FRC0805J102 TS") (field (name "Manufacturer") "FOJAN(富捷)"))
      (libsource (lib "easyedapro") (part "FRC0805J102 TS"))
    )
    (comp (ref "R34")
      (value "2kΩ")
      (footprint "easyedapro:R0805")
      (description "电阻类型:厚膜电阻;阻值:2kΩ;精度:±1%;功率:125mW;最大工作电压:150V;温度系数:±100ppm/°C;")
      (fields
        (field (name "Manufacturer Part") "0805W8F2001T5E")
        (field (name "Manufacturer") "UNI-ROYAL(厚声)")
      )
      (libsource (lib "easyedapro") (part "0805W8F2001T5E"))
    )
    (comp (ref "R35")
      (value "0Ω")
      (footprint "easyedapro:R0603")
      (description "电阻类型:厚膜电阻;阻值:0Ω;精度:±5%;功率:100mW;最大工作电压:75V;")
      (fields (field (name "Manufacturer Part") "FRC0603P000 TS") (field (name "Manufacturer") "FOJAN(富捷)"))
      (libsource (lib "easyedapro") (part "FRC0603P000 TS"))
    )
    (comp (ref "R36")
      (value "0Ω")
      (footprint "easyedapro:R0603")
      (description "电阻类型:厚膜电阻;阻值:0Ω;精度:±5%;功率:100mW;最大工作电压:75V;")
      (fields (field (name "Manufacturer Part") "FRC0603P000 TS") (field (name "Manufacturer") "FOJAN(富捷)"))
      (libsource (lib "easyedapro") (part "FRC0603P000 TS"))
    )
    (comp (ref "U1")
      (value "MPY634KU")
      (footprint "easyedapro:SOIC-16_L10.3-W7.5-P1.27-LS10.3-BL")
      (description "象限:四象限;带宽:-;")
      (fields (field (name "Manufacturer") "TI(德州仪器)"))
      (libsource (lib "easyedapro") (part "MPY634KU"))
    )
    (comp (ref "U3")
      (value "MPY634KU")
      (footprint "easyedapro:SOIC-16_L10.3-W7.5-P1.27-LS10.3-BL")
      (description "象限:四象限;带宽:-;")
      (fields (field (name "Manufacturer") "TI(德州仪器)"))
      (libsource (lib "easyedapro") (part "MPY634KU"))
    )
    (comp (ref "U4")
      (value "OPA227UA/2K5")
      (footprint "easyedapro:SOIC-8_L4.9-W3.9-P1.27-LS6.0-BL")
      (description "放大器数:单路;增益带宽积(GBP):8MHz;输入偏置电流(Ib):2.5nA;压摆率(SR):2.3V/us;轨到轨:-;")
      (fields (field (name "Manufacturer") "TI(德州仪器)"))
      (libsource (lib "easyedapro") (part "OPA227UA/2K5"))
    )
    (comp (ref "U5")
      (value "OPA227UA/2K5")
      (footprint "easyedapro:SOIC-8_L4.9-W3.9-P1.27-LS6.0-BL")
      (description "放大器数:单路;增益带宽积(GBP):8MHz;输入偏置电流(Ib):2.5nA;压摆率(SR):2.3V/us;轨到轨:-;")
      (fields (field (name "Manufacturer") "TI(德州仪器)"))
      (libsource (lib "easyedapro") (part "OPA227UA/2K5"))
    )
  )
  (nets
    (net (code "1") (name "/+5V") (class "Default")
      (node (ref "C10") (pin "1") (pinfunction "1_1") (pintype "unspecified"))
      (node (ref "C17") (pin "1") (pinfunction "1_1") (pintype "unspecified"))
      (node (ref "R31") (pin "1") (pinfunction "1_1") (pintype "input"))
      (node (ref "R32") (pin "2") (pinfunction "2_2") (pintype "unspecified"))
      (node (ref "U4") (pin "7") (pinfunction "VCC_7") (pintype "unspecified"))
      (node (ref "U5") (pin "7") (pinfunction "VCC_7") (pintype "unspecified"))
    )
    (net (code "2") (name "/+15V") (class "Default")
      (node (ref "C1") (pin "1") (pinfunction "1_1") (pintype "unspecified"))
      (node (ref "C12") (pin "1") (pinfunction "1_1") (pintype "unspecified"))
      (node (ref "C3") (pin "2") (pinfunction "2_2") (pintype "input"))
      (node (ref "C5") (pin "1") (pinfunction "1_1") (pintype "unspecified"))
      (node (ref "CN1") (pin "1") (pinfunction "1_1") (pintype "unspecified"))
      (node (ref "R1") (pin "1") (pinfunction "1_1") (pintype "input"))
      (node (ref "R17") (pin "1") (pinfunction "1_1") (pintype "input"))
      (node (ref "R3") (pin "1") (pinfunction "1_1") (pintype "input"))
      (node (ref "R31") (pin "2") (pinfunction "2_2") (pintype "input"))
      (node (ref "U1") (pin "16") (pinfunction "+VS_16") (pintype "unspecified"))
      (node (ref "U3") (pin "16") (pinfunction "+VS_16") (pintype "unspecified"))
    )
    (net (code "3") (name "/-5V") (class "Default")
      (node (ref "C11") (pin "1") (pinfunction "1_1") (pintype "unspecified"))
      (node (ref "C18") (pin "1") (pinfunction "1_1") (pintype "unspecified"))
      (node (ref "R33") (pin "1") (pinfunction "1_1") (pintype "unspecified"))
      (node (ref "R34") (pin "2") (pinfunction "2_2") (pintype "input"))
      (node (ref "U4") (pin "4") (pinfunction "VSS_4") (pintype "unspecified"))
      (node (ref "U5") (pin "4") (pinfunction "VSS_4") (pintype "unspecified"))
    )
    (net (code "4") (name "/-15V") (class "Default")
      (node (ref "C13") (pin "2") (pinfunction "2_2") (pintype "unspecified"))
      (node (ref "C2") (pin "2") (pinfunction "2_2") (pintype "unspecified"))
      (node (ref "C4") (pin "1") (pinfunction "1_1") (pintype "input"))
      (node (ref "C6") (pin "2") (pinfunction "2_2") (pintype "unspecified"))
      (node (ref "CN1") (pin "3") (pinfunction "3_3") (pintype "unspecified"))
      (node (ref "LED2") (pin "2") (pinfunction "-_2") (pintype "unspecified"))
      (node (ref "R10") (pin "1") (pinfunction "1_1") (pintype "input"))
      (node (ref "R17") (pin "3") (pinfunction "3_3") (pintype "input"))
      (node (ref "R24") (pin "1") (pinfunction "1_1") (pintype "input"))
      (node (ref "R3") (pin "3") (pinfunction "3_3") (pintype "input"))
      (node (ref "R34") (pin "1") (pinfunction "1_1") (pintype "input"))
      (node (ref "U1") (pin "10") (pinfunction "–VS_10") (pintype "unspecified"))
      (node (ref "U3") (pin "10") (pinfunction "–VS_10") (pintype "unspecified"))
    )
    (net (code "5") (name "/OUTPUT1") (class "Default")
      (node (ref "OUTPUT1") (pin "5") (pinfunction "5_5") (pintype "unspecified"))
      (node (ref "R11") (pin "2") (pinfunction "2_2") (pintype "unspecified"))
      (node (ref "R14") (pin "1") (pinfunction "1_1") (pintype "unspecified"))
    )
    (net (code "6") (name "/OUTPUT3") (class "Default")
      (node (ref "OUTPUT3") (pin "5") (pinfunction "5_5") (pintype "unspecified"))
      (node (ref "R25") (pin "2") (pinfunction "2_2") (pintype "unspecified"))
      (node (ref "R28") (pin "1") (pinfunction "1_1") (pintype "unspecified"))
    )
    (net (code "7") (name "/SF1") (class "Default")
      (node (ref "ISO1") (pin "1") (pinfunction "1_1") (pintype "unspecified"))
      (node (ref "R9") (pin "1") (pinfunction "1_1") (pintype "input"))
    )
    (net (code "8") (name "/SF2") (class "Default")
      (node (ref "ISO6") (pin "1") (pinfunction "1_1") (pintype "unspecified"))
      (node (ref "R23") (pin "1") (pinfunction "1_1") (pintype "input"))
    )
    (net (code "9") (name "GND") (class "Default")
      (node (ref "C1") (pin "2") (pinfunction "2_2") (pintype "unspecified"))
      (node (ref "C10") (pin "2") (pinfunction "2_2") (pintype "unspecified"))
      (node (ref "C11") (pin "2") (pinfunction "2_2") (pintype "unspecified"))
      (node (ref "C12") (pin "2") (pinfunction "2_2") (pintype "unspecified"))
      (node (ref "C13") (pin "1") (pinfunction "1_1") (pintype "unspecified"))
      (node (ref "C14") (pin "1") (pinfunction "1_1") (pintype "input"))
      (node (ref "C16") (pin "1") (pinfunction "1_1") (pintype "input"))
      (node (ref "C17") (pin "2") (pinfunction "2_2") (pintype "unspecified"))
      (node (ref "C18") (pin "2") (pinfunction "2_2") (pintype "unspecified"))
      (node (ref "C2") (pin "1") (pinfunction "1_1") (pintype "unspecified"))
      (node (ref "C3") (pin "1") (pinfunction "1_1") (pintype "input"))
      (node (ref "C4") (pin "2") (pinfunction "2_2") (pintype "input"))
      (node (ref "C5") (pin "2") (pinfunction "2_2") (pintype "unspecified"))
      (node (ref "C6") (pin "1") (pinfunction "1_1") (pintype "unspecified"))
      (node (ref "C7") (pin "1") (pinfunction "1_1") (pintype "input"))
      (node (ref "C9") (pin "1") (pinfunction "1_1") (pintype "input"))
      (node (ref "CN1") (pin "2") (pinfunction "2_2") (pintype "unspecified"))
      (node (ref "INPUT_X1") (pin "1") (pinfunction "1_1") (pintype "unspecified"))
      (node (ref "INPUT_X1") (pin "2") (pinfunction "2_2") (pintype "unspecified"))
      (node (ref "INPUT_X1") (pin "3") (pinfunction "3_3") (pintype "unspecified"))
      (node (ref "INPUT_X1") (pin "4") (pinfunction "4_4") (pintype "unspecified"))
      (node (ref "INPUT_X2") (pin "1") (pinfunction "1_1") (pintype "unspecified"))
      (node (ref "INPUT_X2") (pin "2") (pinfunction "2_2") (pintype "unspecified"))
      (node (ref "INPUT_X2") (pin "3") (pinfunction "3_3") (pintype "unspecified"))
      (node (ref "INPUT_X2") (pin "4") (pinfunction "4_4") (pintype "unspecified"))
      (node (ref "INPUT_Y1") (pin "1") (pinfunction "1_1") (pintype "unspecified"))
      (node (ref "INPUT_Y1") (pin "2") (pinfunction "2_2") (pintype "unspecified"))
      (node (ref "INPUT_Y1") (pin "3") (pinfunction "3_3") (pintype "unspecified"))
      (node (ref "INPUT_Y1") (pin "4") (pinfunction "4_4") (pintype "unspecified"))
      (node (ref "INPUT_Y2") (pin "1") (pinfunction "1_1") (pintype "unspecified"))
      (node (ref "INPUT_Y2") (pin "2") (pinfunction "2_2") (pintype "unspecified"))
      (node (ref "INPUT_Y2") (pin "3") (pinfunction "3_3") (pintype "unspecified"))
      (node (ref "INPUT_Y2") (pin "4") (pinfunction "4_4") (pintype "unspecified"))
      (node (ref "INPUT_Z1") (pin "1") (pinfunction "1_1") (pintype "unspecified"))
      (node (ref "INPUT_Z1") (pin "2") (pinfunction "2_2") (pintype "unspecified"))
      (node (ref "INPUT_Z1") (pin "3") (pinfunction "3_3") (pintype "unspecified"))
      (node (ref "INPUT_Z1") (pin "4") (pinfunction "4_4") (pintype "unspecified"))
      (node (ref "INPUT_Z2") (pin "1") (pinfunction "1_1") (pintype "unspecified"))
      (node (ref "INPUT_Z2") (pin "2") (pinfunction "2_2") (pintype "unspecified"))
      (node (ref "INPUT_Z2") (pin "3") (pinfunction "3_3") (pintype "unspecified"))
      (node (ref "INPUT_Z2") (pin "4") (pinfunction "4_4") (pintype "unspecified"))
      (node (ref "LED1") (pin "2") (pinfunction "-_2") (pintype "unspecified"))
      (node (ref "OUTPUT1") (pin "1") (pinfunction "1_1") (pintype "unspecified"))
      (node (ref "OUTPUT1") (pin "2") (pinfunction "2_2") (pintype "unspecified"))
      (node (ref "OUTPUT1") (pin "3") (pinfunction "3_3") (pintype "unspecified"))
      (node (ref "OUTPUT1") (pin "4") (pinfunction "4_4") (pintype "unspecified"))
      (node (ref "OUTPUT2") (pin "1") (pinfunction "1_1") (pintype "unspecified"))
      (node (ref "OUTPUT2") (pin "2") (pinfunction "2_2") (pintype "unspecified"))
      (node (ref "OUTPUT2") (pin "3") (pinfunction "3_3") (pintype "unspecified"))
      (node (ref "OUTPUT2") (pin "4") (pinfunction "4_4") (pintype "unspecified"))
      (node (ref "OUTPUT3") (pin "1") (pinfunction "1_1") (pintype "unspecified"))
      (node (ref "OUTPUT3") (pin "2") (pinfunction "2_2") (pintype "unspecified"))
      (node (ref "OUTPUT3") (pin "3") (pinfunction "3_3") (pintype "unspecified"))
      (node (ref "OUTPUT3") (pin "4") (pinfunction "4_4") (pintype "unspecified"))
      (node (ref "OUTPUT4") (pin "1") (pinfunction "1_1") (pintype "unspecified"))
      (node (ref "OUTPUT4") (pin "2") (pinfunction "2_2") (pintype "unspecified"))
      (node (ref "OUTPUT4") (pin "3") (pinfunction "3_3") (pintype "unspecified"))
      (node (ref "OUTPUT4") (pin "4") (pinfunction "4_4") (pintype "unspecified"))
      (node (ref "R13") (pin "2") (pinfunction "2_2") (pintype "unspecified"))
      (node (ref "R19") (pin "1") (pinfunction "1_1") (pintype "unspecified"))
      (node (ref "R2") (pin "1") (pinfunction "1_1") (pintype "input"))
      (node (ref "R22") (pin "1") (pinfunction "1_1") (pintype "unspecified"))
      (node (ref "R27") (pin "2") (pinfunction "2_2") (pintype "unspecified"))
      (node (ref "R32") (pin "1") (pinfunction "1_1") (pintype "unspecified"))
      (node (ref "R33") (pin "2") (pinfunction "2_2") (pintype "unspecified"))
      (node (ref "R5") (pin "1") (pinfunction "1_1") (pintype "unspecified"))
      (node (ref "R8") (pin "1") (pinfunction "1_1") (pintype "unspecified"))
    )
    (net (code "10") (name "Net-(C7-Pad2)") (class "Default")
      (node (ref "C7") (pin "2") (pinfunction "2_2") (pintype "input"))
      (node (ref "R14") (pin "2") (pinfunction "2_2") (pintype "unspecified"))
      (node (ref "R15") (pin "2") (pinfunction "2_2") (pintype "unspecified"))
    )
    (net (code "11") (name "Net-(C8-Pad1)") (class "Default")
      (node (ref "C8") (pin "1") (pinfunction "1_1") (pintype "input"))
      (node (ref "R15") (pin "1") (pinfunction "1_1") (pintype "unspecified"))
      (node (ref "R16") (pin "2") (pinfunction "2_2") (pintype "unspecified"))
    )
    (net (code "12") (name "Net-(C14-Pad2)") (class "Default")
      (node (ref "C14") (pin "2") (pinfunction "2_2") (pintype "input"))
      (node (ref "R28") (pin "2") (pinfunction "2_2") (pintype "unspecified"))
      (node (ref "R29") (pin "2") (pinfunction "2_2") (pintype "unspecified"))
    )
    (net (code "13") (name "Net-(C15-Pad1)") (class "Default")
      (node (ref "C15") (pin "1") (pinfunction "1_1") (pintype "input"))
      (node (ref "R29") (pin "1") (pinfunction "1_1") (pintype "unspecified"))
      (node (ref "R30") (pin "2") (pinfunction "2_2") (pintype "unspecified"))
    )
    (net (code "14") (name "Net-(INPUT_X1-Pad5)") (class "Default")
      (node (ref "INPUT_X1") (pin "5") (pinfunction "5_5") (pintype "unspecified"))
      (node (ref "R6") (pin "1") (pinfunction "1_1") (pintype "unspecified"))
    )
    (net (code "15") (name "Net-(INPUT_X2-Pad5)") (class "Default")
      (node (ref "INPUT_X2") (pin "5") (pinfunction "5_5") (pintype "unspecified"))
      (node (ref "R20") (pin "1") (pinfunction "1_1") (pintype "unspecified"))
    )
    (net (code "16") (name "Net-(INPUT_Y1-Pad5)") (class "Default")
      (node (ref "INPUT_Y1") (pin "5") (pinfunction "5_5") (pintype "unspecified"))
      (node (ref "R7") (pin "1") (pinfunction "1_1") (pintype "unspecified"))
    )
    (net (code "17") (name "Net-(INPUT_Y2-Pad5)") (class "Default")
      (node (ref "INPUT_Y2") (pin "5") (pinfunction "5_5") (pintype "unspecified"))
      (node (ref "R21") (pin "1") (pinfunction "1_1") (pintype "unspecified"))
    )
    (net (code "18") (name "Net-(INPUT_Z1-Pad5)") (class "Default")
      (node (ref "INPUT_Z1") (pin "5") (pinfunction "5_5") (pintype "unspecified"))
      (node (ref "R12") (pin "1") (pinfunction "1_1") (pintype "unspecified"))
    )
    (net (code "19") (name "Net-(INPUT_Z2-Pad5)") (class "Default")
      (node (ref "INPUT_Z2") (pin "5") (pinfunction "5_5") (pintype "unspecified"))
      (node (ref "R26") (pin "1") (pinfunction "1_1") (pintype "unspecified"))
    )
    (net (code "20") (name "Net-(LED1-+)") (class "Default")
      (node (ref "LED1") (pin "1") (pinfunction "+_1") (pintype "unspecified"))
      (node (ref "R1") (pin "2") (pinfunction "2_2") (pintype "input"))
    )
    (net (code "21") (name "Net-(LED2-+)") (class "Default")
      (node (ref "LED2") (pin "1") (pinfunction "+_1") (pintype "unspecified"))
      (node (ref "R2") (pin "2") (pinfunction "2_2") (pintype "input"))
    )
    (net (code "22") (name "Net-(OUTPUT2-Pad5)") (class "Default")
      (node (ref "OUTPUT2") (pin "5") (pinfunction "5_5") (pintype "unspecified"))
      (node (ref "R35") (pin "1") (pinfunction "1_1") (pintype "unspecified"))
    )
    (net (code "23") (name "Net-(OUTPUT4-Pad5)") (class "Default")
      (node (ref "OUTPUT4") (pin "5") (pinfunction "5_5") (pintype "unspecified"))
      (node (ref "R36") (pin "1") (pinfunction "1_1") (pintype "unspecified"))
    )
    (net (code "24") (name "Net-(R3-Pad2)") (class "Default")
      (node (ref "R3") (pin "2") (pinfunction "2_2") (pintype "input"))
      (node (ref "R4") (pin "2") (pinfunction "2_2") (pintype "input"))
    )
    (net (code "25") (name "Net-(R10-Pad2)") (class "Default")
      (node (ref "R10") (pin "2") (pinfunction "2_2") (pintype "input"))
      (node (ref "R10") (pin "3") (pinfunction "3_3") (pintype "input"))
      (node (ref "R9") (pin "2") (pinfunction "2_2") (pintype "input"))
    )
    (net (code "26") (name "Net-(R17-Pad2)") (class "Default")
      (node (ref "R17") (pin "2") (pinfunction "2_2") (pintype "input"))
      (node (ref "R18") (pin "2") (pinfunction "2_2") (pintype "input"))
    )
    (net (code "27") (name "Net-(R23-Pad2)") (class "Default")
      (node (ref "R23") (pin "2") (pinfunction "2_2") (pintype "input"))
      (node (ref "R24") (pin "2") (pinfunction "2_2") (pintype "input"))
      (node (ref "R24") (pin "3") (pinfunction "3_3") (pintype "input"))
    )
    (net (code "28") (name "Net-(U1-Output)") (class "Default")
      (node (ref "ISO3") (pin "1") (pinfunction "1_1") (pintype "unspecified"))
      (node (ref "ISO5") (pin "2") (pinfunction "2_2") (pintype "unspecified"))
      (node (ref "R11") (pin "1") (pinfunction "1_1") (pintype "unspecified"))
      (node (ref "U1") (pin "14") (pinfunction "Output_14") (pintype "unspecified"))
    )
    (net (code "29") (name "Net-(U1-Scale_Factor)") (class "Default")
      (node (ref "ISO1") (pin "2") (pinfunction "2_2") (pintype "unspecified"))
      (node (ref "U1") (pin "4") (pinfunction "Scale_Factor_4") (pintype "unspecified"))
    )
    (net (code "30") (name "Net-(U1-X1_Input)") (class "Default")
      (node (ref "ISO2") (pin "2") (pinfunction "2_2") (pintype "unspecified"))
      (node (ref "R6") (pin "2") (pinfunction "2_2") (pintype "unspecified"))
      (node (ref "U1") (pin "1") (pinfunction "X1_Input_1") (pintype "unspecified"))
    )
    (net (code "31") (name "Net-(U1-X2_Input)") (class "Default")
      (node (ref "R4") (pin "1") (pinfunction "1_1") (pintype "input"))
      (node (ref "R5") (pin "2") (pinfunction "2_2") (pintype "unspecified"))
      (node (ref "U1") (pin "2") (pinfunction "X2_Input_2") (pintype "unspecified"))
    )
    (net (code "32") (name "Net-(U1-Y1_Input)") (class "Default")
      (node (ref "ISO2") (pin "1") (pinfunction "1_1") (pintype "unspecified"))
      (node (ref "ISO4") (pin "2") (pinfunction "2_2") (pintype "unspecified"))
      (node (ref "R7") (pin "2") (pinfunction "2_2") (pintype "unspecified"))
      (node (ref "U1") (pin "6") (pinfunction "Y1_Input_6") (pintype "unspecified"))
    )
    (net (code "33") (name "Net-(U1-Y2_Input)") (class "Default")
      (node (ref "ISO3") (pin "2") (pinfunction "2_2") (pintype "unspecified"))
      (node (ref "R8") (pin "2") (pinfunction "2_2") (pintype "unspecified"))
      (node (ref "U1") (pin "7") (pinfunction "Y2_Input_7") (pintype "unspecified"))
    )
    (net (code "34") (name "Net-(U1-Z1_Input)") (class "Default")
      (node (ref "ISO5") (pin "1") (pinfunction "1_1") (pintype "unspecified"))
      (node (ref "R12") (pin "2") (pinfunction "2_2") (pintype "unspecified"))
      (node (ref "U1") (pin "13") (pinfunction "Z1_Input_13") (pintype "unspecified"))
    )
    (net (code "35") (name "Net-(U1-Z2_Input)") (class "Default")
      (node (ref "ISO4") (pin "1") (pinfunction "1_1") (pintype "unspecified"))
      (node (ref "R13") (pin "1") (pinfunction "1_1") (pintype "unspecified"))
      (node (ref "U1") (pin "12") (pinfunction "Z2_Input_12") (pintype "unspecified"))
    )
    (net (code "36") (name "Net-(U3-Output)") (class "Default")
      (node (ref "ISO10") (pin "2") (pinfunction "2_2") (pintype "unspecified"))
      (node (ref "ISO8") (pin "1") (pinfunction "1_1") (pintype "unspecified"))
      (node (ref "R25") (pin "1") (pinfunction "1_1") (pintype "unspecified"))
      (node (ref "U3") (pin "14") (pinfunction "Output_14") (pintype "unspecified"))
    )
    (net (code "37") (name "Net-(U3-Scale_Factor)") (class "Default")
      (node (ref "ISO6") (pin "2") (pinfunction "2_2") (pintype "unspecified"))
      (node (ref "U3") (pin "4") (pinfunction "Scale_Factor_4") (pintype "unspecified"))
    )
    (net (code "38") (name "Net-(U3-X1_Input)") (class "Default")
      (node (ref "ISO7") (pin "2") (pinfunction "2_2") (pintype "unspecified"))
      (node (ref "R20") (pin "2") (pinfunction "2_2") (pintype "unspecified"))
      (node (ref "U3") (pin "1") (pinfunction "X1_Input_1") (pintype "unspecified"))
    )
    (net (code "39") (name "Net-(U3-X2_Input)") (class "Default")
      (node (ref "R18") (pin "1") (pinfunction "1_1") (pintype "input"))
      (node (ref "R19") (pin "2") (pinfunction "2_2") (pintype "unspecified"))
      (node (ref "U3") (pin "2") (pinfunction "X2_Input_2") (pintype "unspecified"))
    )
    (net (code "40") (name "Net-(U3-Y1_Input)") (class "Default")
      (node (ref "ISO7") (pin "1") (pinfunction "1_1") (pintype "unspecified"))
      (node (ref "ISO9") (pin "2") (pinfunction "2_2") (pintype "unspecified"))
      (node (ref "R21") (pin "2") (pinfunction "2_2") (pintype "unspecified"))
      (node (ref "U3") (pin "6") (pinfunction "Y1_Input_6") (pintype "unspecified"))
    )
    (net (code "41") (name "Net-(U3-Y2_Input)") (class "Default")
      (node (ref "ISO8") (pin "2") (pinfunction "2_2") (pintype "unspecified"))
      (node (ref "R22") (pin "2") (pinfunction "2_2") (pintype "unspecified"))
      (node (ref "U3") (pin "7") (pinfunction "Y2_Input_7") (pintype "unspecified"))
    )
    (net (code "42") (name "Net-(U3-Z1_Input)") (class "Default")
      (node (ref "ISO10") (pin "1") (pinfunction "1_1") (pintype "unspecified"))
      (node (ref "R26") (pin "2") (pinfunction "2_2") (pintype "unspecified"))
      (node (ref "U3") (pin "13") (pinfunction "Z1_Input_13") (pintype "unspecified"))
    )
    (net (code "43") (name "Net-(U3-Z2_Input)") (class "Default")
      (node (ref "ISO9") (pin "1") (pinfunction "1_1") (pintype "unspecified"))
      (node (ref "R27") (pin "1") (pinfunction "1_1") (pintype "unspecified"))
      (node (ref "U3") (pin "12") (pinfunction "Z2_Input_12") (pintype "unspecified"))
    )
    (net (code "44") (name "Net-(U4-OUT)") (class "Default")
      (node (ref "C8") (pin "2") (pinfunction "2_2") (pintype "input"))
      (node (ref "R35") (pin "2") (pinfunction "2_2") (pintype "unspecified"))
      (node (ref "U4") (pin "2") (pinfunction "VIN-_2") (pintype "unspecified"))
      (node (ref "U4") (pin "6") (pinfunction "OUT_6") (pintype "output"))
    )
    (net (code "45") (name "Net-(U4-VIN+)") (class "Default")
      (node (ref "C9") (pin "2") (pinfunction "2_2") (pintype "input"))
      (node (ref "R16") (pin "1") (pinfunction "1_1") (pintype "unspecified"))
      (node (ref "U4") (pin "3") (pinfunction "VIN+_3") (pintype "unspecified"))
    )
    (net (code "46") (name "Net-(U5-OUT)") (class "Default")
      (node (ref "C15") (pin "2") (pinfunction "2_2") (pintype "input"))
      (node (ref "R36") (pin "2") (pinfunction "2_2") (pintype "unspecified"))
      (node (ref "U5") (pin "2") (pinfunction "VIN-_2") (pintype "unspecified"))
      (node (ref "U5") (pin "6") (pinfunction "OUT_6") (pintype "output"))
    )
    (net (code "47") (name "Net-(U5-VIN+)") (class "Default")
      (node (ref "C16") (pin "2") (pinfunction "2_2") (pintype "input"))
      (node (ref "R30") (pin "1") (pinfunction "1_1") (pintype "unspecified"))
      (node (ref "U5") (pin "3") (pinfunction "VIN+_3") (pintype "unspecified"))
    )
    (net (code "48") (name "unconnected-(U1-NC-Pad3)") (class "Default")
      (node (ref "U1") (pin "3") (pinfunction "NC_3") (pintype "unspecified+no_connect"))
    )
    (net (code "49") (name "unconnected-(U1-NC-Pad5)") (class "Default")
      (node (ref "U1") (pin "5") (pinfunction "NC_5") (pintype "unspecified+no_connect"))
    )
    (net (code "50") (name "unconnected-(U1-NC-Pad8)") (class "Default")
      (node (ref "U1") (pin "8") (pinfunction "NC_8") (pintype "unspecified+no_connect"))
    )
    (net (code "51") (name "unconnected-(U1-NC-Pad9)") (class "Default")
      (node (ref "U1") (pin "9") (pinfunction "NC_9") (pintype "unspecified+no_connect"))
    )
    (net (code "52") (name "unconnected-(U1-NC-Pad11)") (class "Default")
      (node (ref "U1") (pin "11") (pinfunction "NC_11") (pintype "unspecified+no_connect"))
    )
    (net (code "53") (name "unconnected-(U1-NC-Pad15)") (class "Default")
      (node (ref "U1") (pin "15") (pinfunction "NC_15") (pintype "unspecified+no_connect"))
    )
    (net (code "54") (name "unconnected-(U3-NC-Pad3)") (class "Default")
      (node (ref "U3") (pin "3") (pinfunction "NC_3") (pintype "unspecified+no_connect"))
    )
    (net (code "55") (name "unconnected-(U3-NC-Pad5)") (class "Default")
      (node (ref "U3") (pin "5") (pinfunction "NC_5") (pintype "unspecified+no_connect"))
    )
    (net (code "56") (name "unconnected-(U3-NC-Pad8)") (class "Default")
      (node (ref "U3") (pin "8") (pinfunction "NC_8") (pintype "unspecified+no_connect"))
    )
    (net (code "57") (name "unconnected-(U3-NC-Pad9)") (class "Default")
      (node (ref "U3") (pin "9") (pinfunction "NC_9") (pintype "unspecified+no_connect"))
    )
    (net (code "58") (name "unconnected-(U3-NC-Pad11)") (class "Default")
      (node (ref "U3") (pin "11") (pinfunction "NC_11") (pintype "unspecified+no_connect"))
    )
    (net (code "59") (name "unconnected-(U3-NC-Pad15)") (class "Default")
      (node (ref "U3") (pin "15") (pinfunction "NC_15") (pintype "unspecified+no_connect"))
    )
    (net (code "60") (name "unconnected-(U4-NC-Pad5)") (class "Default")
      (node (ref "U4") (pin "5") (pinfunction "NC_5") (pintype "unspecified+no_connect"))
    )
    (net (code "61") (name "unconnected-(U4-TRIM-Pad1)") (class "Default")
      (node (ref "U4") (pin "1") (pinfunction "TRIM_1") (pintype "unspecified+no_connect"))
    )
    (net (code "62") (name "unconnected-(U4-TRIM-Pad8)") (class "Default")
      (node (ref "U4") (pin "8") (pinfunction "TRIM_8") (pintype "unspecified+no_connect"))
    )
    (net (code "63") (name "unconnected-(U5-NC-Pad5)") (class "Default")
      (node (ref "U5") (pin "5") (pinfunction "NC_5") (pintype "unspecified+no_connect"))
    )
    (net (code "64") (name "unconnected-(U5-TRIM-Pad1)") (class "Default")
      (node (ref "U5") (pin "1") (pinfunction "TRIM_1") (pintype "unspecified+no_connect"))
    )
    (net (code "65") (name "unconnected-(U5-TRIM-Pad8)") (class "Default")
      (node (ref "U5") (pin "8") (pinfunction "TRIM_8") (pintype "unspecified+no_connect"))
    )
  )
)
